# PROC099A_Decoupling_Caps_Reference.net
KiCad netlist of a schematic drawn in Altium Designer
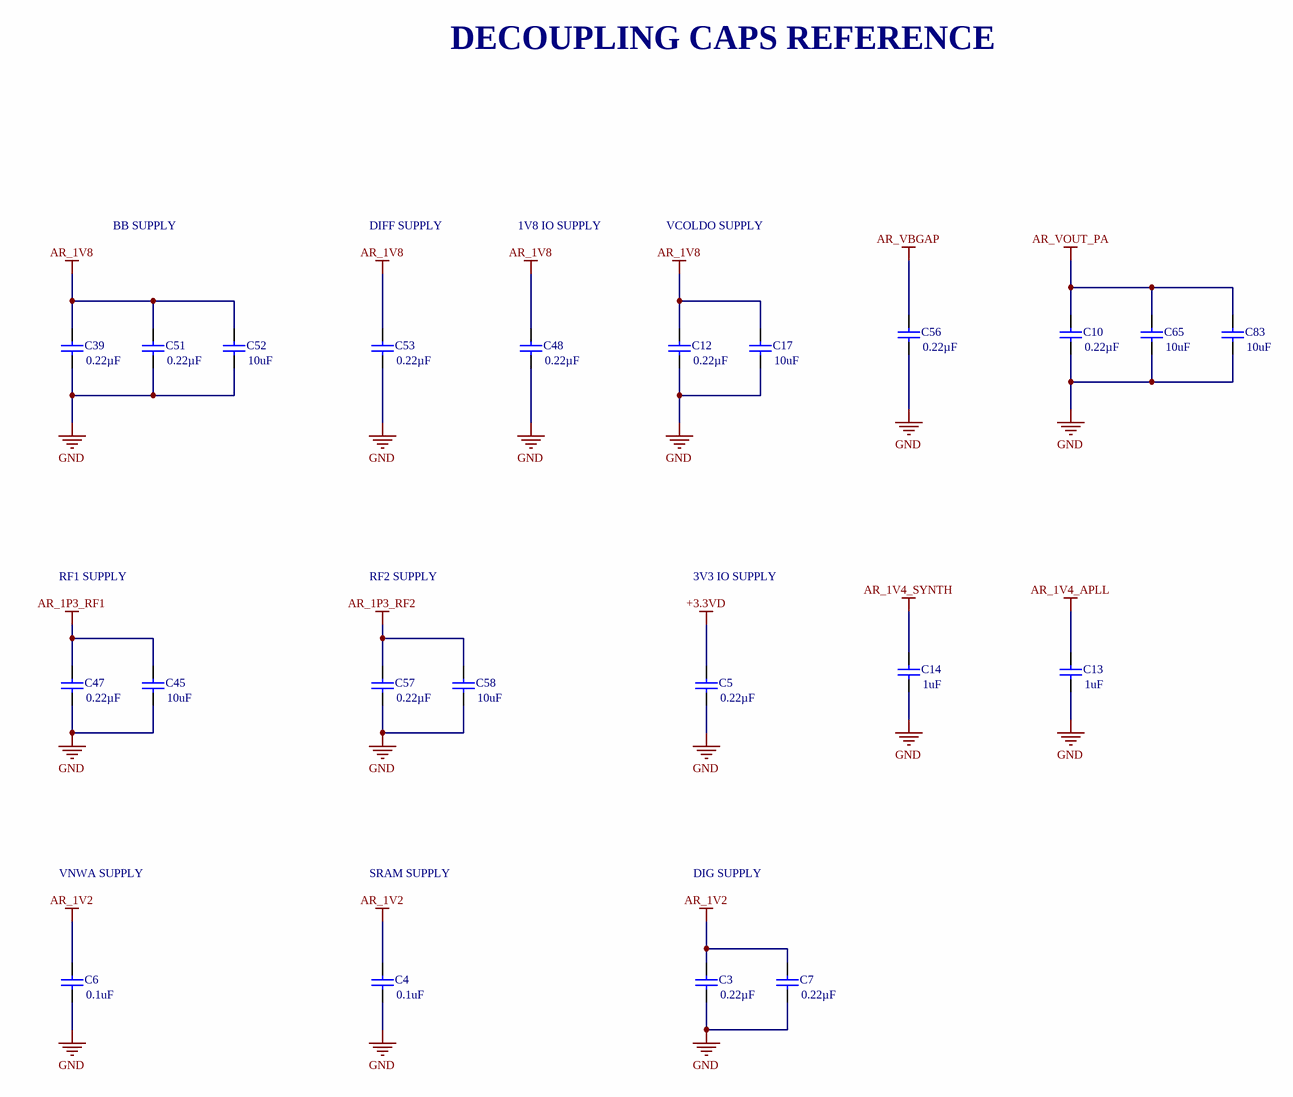
[diagram p0: PROC099A_Decoupling_Caps_Reference.SchDoc]

(export (version "E")
  (design (tool "Eeschema 10.0.6"))
  (components
    (comp (ref "C3")
      (value "GCM155R71C224KE02D")
      (footprint "0402L")
      (description "CAP, CERM, 0.22 µF, 16 V,+/- 10%, X7R, AEC-Q200 Grade 1, 0402")
      (fields (field (name "MANUFACTURER") "MuRata") (field (name "VALUEDISPLAYED") "0.22µF"))
      (libsource (lib "Altium Vault - TI") (part "CMP-0078265-1"))
    )
    (comp (ref "C4")
      (value "GCM155R71C104KA55D")
      (footprint "0402L")
      (description "CAP, CERM, 0.1 uF, 16 V, +/- 10%, X7R, 0402")
      (fields
        (field (name "MANUFACTURER") "MuRata")
        (field (name "VALUEDISPLAYED") "0.1uF")
        (field (name "PUBLISHER") "Texas Instruments")
      )
      (libsource (lib "Altium Vault - TI") (part "CMP-0006351-2"))
    )
    (comp (ref "C5")
      (value "GCM155R71C224KE02D")
      (footprint "0402L")
      (description "CAP, CERM, 0.22 µF, 16 V,+/- 10%, X7R, AEC-Q200 Grade 1, 0402")
      (fields (field (name "MANUFACTURER") "MuRata") (field (name "VALUEDISPLAYED") "0.22µF"))
      (libsource (lib "Altium Vault - TI") (part "CMP-0078265-1"))
    )
    (comp (ref "C6")
      (value "GCM155R71C104KA55D")
      (footprint "0402")
      (description "CAP, CERM, 0.1 uF, 16 V, +/- 10%, X7R, 0402")
      (fields
        (field (name "MANUFACTURER") "MuRata")
        (field (name "VALUEDISPLAYED") "0.1uF")
        (field (name "PUBLISHER") "Texas Instruments")
      )
      (libsource (lib "Altium Vault - TI") (part "Capacitor"))
    )
    (comp (ref "C7")
      (value "GCM155R71C224KE02D")
      (footprint "0402L")
      (description "CAP, CERM, 0.22 µF, 16 V,+/- 10%, X7R, AEC-Q200 Grade 1, 0402")
      (fields (field (name "MANUFACTURER") "MuRata") (field (name "VALUEDISPLAYED") "0.22µF"))
      (libsource (lib "Altium Vault - TI") (part "CMP-0078265-1"))
    )
    (comp (ref "C10")
      (value "GCM155R71C224KE02D")
      (footprint "0402")
      (description "CAP, CERM, 0.22 µF, 16 V,+/- 10%, X7R, AEC-Q200 Grade 1, 0402")
      (fields (field (name "MANUFACTURER") "MuRata") (field (name "VALUEDISPLAYED") "0.22µF"))
      (libsource (lib "Altium Vault - TI") (part "Capacitor"))
    )
    (comp (ref "C12")
      (value "GCM155R71C224KE02D")
      (footprint "0402")
      (description "CAP, CERM, 0.22 µF, 16 V,+/- 10%, X7R, AEC-Q200 Grade 1, 0402")
      (fields (field (name "MANUFACTURER") "MuRata") (field (name "VALUEDISPLAYED") "0.22µF"))
      (libsource (lib "Altium Vault - TI") (part "Capacitor"))
    )
    (comp (ref "C13")
      (value "GCM188R71C105KA64D")
      (footprint "0603")
      (description "CAP, CERM, 1 uF, 16 V, +/- 10%, X7R, AEC-Q200 Grade 1, 0603")
      (fields
        (field (name "MANUFACTURER") "MuRata")
        (field (name "VALUEDISPLAYED") "1uF")
        (field (name "PUBLISHER") "Texas Instruments")
      )
      (libsource (lib "Altium Vault - TI") (part "Capacitor"))
    )
    (comp (ref "C14")
      (value "GCM188R71C105KA64D")
      (footprint "0603")
      (description "CAP, CERM, 1 uF, 16 V, +/- 10%, X7R, AEC-Q200 Grade 1, 0603")
      (fields
        (field (name "MANUFACTURER") "MuRata")
        (field (name "VALUEDISPLAYED") "1uF")
        (field (name "PUBLISHER") "Texas Instruments")
      )
      (libsource (lib "Altium Vault - TI") (part "Capacitor"))
    )
    (comp (ref "C17")
      (value "GCM21BR71A106KE22L")
      (footprint "0805_HV")
      (description "CAP, CERM, 10 uF, 10 V, +/- 10%, X7R, 0805")
      (fields
        (field (name "MANUFACTURER") "MuRata")
        (field (name "VALUEDISPLAYED") "10uF")
        (field (name "PUBLISHER") "Texas Instruments")
      )
      (libsource (lib "Altium Vault - TI") (part "Capacitor"))
    )
    (comp (ref "C39")
      (value "GCM155R71C224KE02D")
      (footprint "0402L")
      (description "CAP, CERM, 0.22 µF, 16 V,+/- 10%, X7R, AEC-Q200 Grade 1, 0402")
      (fields (field (name "MANUFACTURER") "MuRata") (field (name "VALUEDISPLAYED") "0.22µF"))
      (libsource (lib "Altium Vault - TI") (part "CMP-0078265-1"))
    )
    (comp (ref "C45")
      (value "GCM21BR71A106KE22L")
      (footprint "0805_HV1")
      (description "CAP, CERM, 10 uF, 10 V, +/- 10%, X7R, 0805")
      (fields
        (field (name "MANUFACTURER") "MuRata")
        (field (name "VALUEDISPLAYED") "10uF")
        (field (name "PUBLISHER") "Texas Instruments")
      )
      (libsource (lib "Altium Vault - TI") (part "CMP-0008017-2"))
    )
    (comp (ref "C47")
      (value "GCM155R71C224KE02D")
      (footprint "0402L")
      (description "CAP, CERM, 0.22 µF, 16 V,+/- 10%, X7R, AEC-Q200 Grade 1, 0402")
      (fields (field (name "MANUFACTURER") "MuRata") (field (name "VALUEDISPLAYED") "0.22µF"))
      (libsource (lib "Altium Vault - TI") (part "CMP-0078265-1"))
    )
    (comp (ref "C48")
      (value "GCM155R71C224KE02D")
      (footprint "0402")
      (description "CAP, CERM, 0.22 µF, 16 V,+/- 10%, X7R, AEC-Q200 Grade 1, 0402")
      (fields (field (name "MANUFACTURER") "MuRata") (field (name "VALUEDISPLAYED") "0.22µF"))
      (libsource (lib "Altium Vault - TI") (part "Capacitor"))
    )
    (comp (ref "C51")
      (value "GCM155R71C224KE02D")
      (footprint "0402")
      (description "CAP, CERM, 0.22 µF, 16 V,+/- 10%, X7R, AEC-Q200 Grade 1, 0402")
      (fields (field (name "MANUFACTURER") "MuRata") (field (name "VALUEDISPLAYED") "0.22µF"))
      (libsource (lib "Altium Vault - TI") (part "Capacitor"))
    )
    (comp (ref "C52")
      (value "GCM21BR71A106KE22L")
      (footprint "0805_HV")
      (description "CAP, CERM, 10 uF, 10 V, +/- 10%, X7R, 0805")
      (fields
        (field (name "MANUFACTURER") "MuRata")
        (field (name "VALUEDISPLAYED") "10uF")
        (field (name "PUBLISHER") "Texas Instruments")
      )
      (libsource (lib "Altium Vault - TI") (part "Capacitor"))
    )
    (comp (ref "C53")
      (value "GCM155R71C224KE02D")
      (footprint "0402")
      (description "CAP, CERM, 0.22 µF, 16 V,+/- 10%, X7R, AEC-Q200 Grade 1, 0402")
      (fields (field (name "MANUFACTURER") "MuRata") (field (name "VALUEDISPLAYED") "0.22µF"))
      (libsource (lib "Altium Vault - TI") (part "Capacitor"))
    )
    (comp (ref "C56")
      (value "GCM155R71C224KE02D")
      (footprint "0402")
      (description "CAP, CERM, 0.22 µF, 16 V,+/- 10%, X7R, AEC-Q200 Grade 1, 0402")
      (fields (field (name "MANUFACTURER") "MuRata") (field (name "VALUEDISPLAYED") "0.22µF"))
      (libsource (lib "Altium Vault - TI") (part "Capacitor"))
    )
    (comp (ref "C57")
      (value "GCM155R71C224KE02D")
      (footprint "0402")
      (description "CAP, CERM, 0.22 µF, 16 V,+/- 10%, X7R, AEC-Q200 Grade 1, 0402")
      (fields (field (name "MANUFACTURER") "MuRata") (field (name "VALUEDISPLAYED") "0.22µF"))
      (libsource (lib "Altium Vault - TI") (part "Capacitor"))
    )
    (comp (ref "C58")
      (value "GCM21BR71A106KE22L")
      (footprint "0805")
      (description "CAP, CERM, 10 uF, 10 V, +/- 10%, X7R, 0805")
      (fields
        (field (name "MANUFACTURER") "MuRata")
        (field (name "VALUEDISPLAYED") "10uF")
        (field (name "PUBLISHER") "Texas Instruments")
      )
      (libsource (lib "Altium Vault - TI") (part "CMP-0008017-2"))
    )
    (comp (ref "C65")
      (value "GCM21BR71A106KE22L")
      (footprint "0805_HV")
      (description "CAP, CERM, 10 uF, 10 V, +/- 10%, X7R, 0805")
      (fields
        (field (name "MANUFACTURER") "MuRata")
        (field (name "VALUEDISPLAYED") "10uF")
        (field (name "PUBLISHER") "Texas Instruments")
      )
      (libsource (lib "Altium Vault - TI") (part "Capacitor"))
    )
    (comp (ref "C83")
      (value "GCM21BR71A106KE22L")
      (footprint "0805_HV")
      (description "CAP, CERM, 10 uF, 10 V, +/- 10%, X7R, 0805")
      (fields
        (field (name "MANUFACTURER") "MuRata")
        (field (name "VALUEDISPLAYED") "10uF")
        (field (name "PUBLISHER") "Texas Instruments")
      )
      (libsource (lib "Altium Vault - TI") (part "Capacitor"))
    )
  )
  (nets
    (net (code "1") (name "+3.3VD") (class "Default")
      (node (ref "C5") (pin "1") (pinfunction "1_1") (pintype "passive"))
    )
    (net (code "2") (name "AR_1P3_RF1") (class "Default")
      (node (ref "C45") (pin "1") (pinfunction "1_1") (pintype "passive"))
      (node (ref "C47") (pin "1") (pinfunction "1_1") (pintype "passive"))
    )
    (net (code "3") (name "AR_1P3_RF2") (class "Default")
      (node (ref "C57") (pin "1") (pinfunction "1_1") (pintype "passive"))
      (node (ref "C58") (pin "1") (pinfunction "1_1") (pintype "passive"))
    )
    (net (code "4") (name "AR_1V2") (class "Default")
      (node (ref "C3") (pin "1") (pinfunction "1_1") (pintype "passive"))
      (node (ref "C4") (pin "1") (pinfunction "1_1") (pintype "passive"))
      (node (ref "C6") (pin "1") (pinfunction "1_1") (pintype "passive"))
      (node (ref "C7") (pin "1") (pinfunction "1_1") (pintype "passive"))
    )
    (net (code "5") (name "AR_1V4_APLL") (class "Default")
      (node (ref "C13") (pin "1") (pinfunction "1_1") (pintype "passive"))
    )
    (net (code "6") (name "AR_1V4_SYNTH") (class "Default")
      (node (ref "C14") (pin "1") (pinfunction "1_1") (pintype "passive"))
    )
    (net (code "7") (name "AR_1V8") (class "Default")
      (node (ref "C12") (pin "1") (pinfunction "1_1") (pintype "passive"))
      (node (ref "C17") (pin "1") (pinfunction "1_1") (pintype "passive"))
      (node (ref "C39") (pin "1") (pinfunction "1_1") (pintype "passive"))
      (node (ref "C48") (pin "1") (pinfunction "1_1") (pintype "passive"))
      (node (ref "C51") (pin "1") (pinfunction "1_1") (pintype "passive"))
      (node (ref "C52") (pin "1") (pinfunction "1_1") (pintype "passive"))
      (node (ref "C53") (pin "1") (pinfunction "1_1") (pintype "passive"))
    )
    (net (code "8") (name "AR_VBGAP") (class "Default")
      (node (ref "C56") (pin "1") (pinfunction "1_1") (pintype "passive"))
    )
    (net (code "9") (name "AR_VOUT_PA") (class "Default")
      (node (ref "C10") (pin "1") (pinfunction "1_1") (pintype "passive"))
      (node (ref "C65") (pin "1") (pinfunction "1_1") (pintype "passive"))
      (node (ref "C83") (pin "1") (pinfunction "1_1") (pintype "passive"))
    )
    (net (code "10") (name "GND") (class "Default")
      (node (ref "C10") (pin "2") (pinfunction "2_2") (pintype "passive"))
      (node (ref "C12") (pin "2") (pinfunction "2_2") (pintype "passive"))
      (node (ref "C13") (pin "2") (pinfunction "2_2") (pintype "passive"))
      (node (ref "C14") (pin "2") (pinfunction "2_2") (pintype "passive"))
      (node (ref "C17") (pin "2") (pinfunction "2_2") (pintype "passive"))
      (node (ref "C3") (pin "2") (pinfunction "2_2") (pintype "passive"))
      (node (ref "C39") (pin "2") (pinfunction "2_2") (pintype "passive"))
      (node (ref "C4") (pin "2") (pinfunction "2_2") (pintype "passive"))
      (node (ref "C45") (pin "2") (pinfunction "2_2") (pintype "passive"))
      (node (ref "C47") (pin "2") (pinfunction "2_2") (pintype "passive"))
      (node (ref "C48") (pin "2") (pinfunction "2_2") (pintype "passive"))
      (node (ref "C5") (pin "2") (pinfunction "2_2") (pintype "passive"))
      (node (ref "C51") (pin "2") (pinfunction "2_2") (pintype "passive"))
      (node (ref "C52") (pin "2") (pinfunction "2_2") (pintype "passive"))
      (node (ref "C53") (pin "2") (pinfunction "2_2") (pintype "passive"))
      (node (ref "C56") (pin "2") (pinfunction "2_2") (pintype "passive"))
      (node (ref "C57") (pin "2") (pinfunction "2_2") (pintype "passive"))
      (node (ref "C58") (pin "2") (pinfunction "2_2") (pintype "passive"))
      (node (ref "C6") (pin "2") (pinfunction "2_2") (pintype "passive"))
      (node (ref "C65") (pin "2") (pinfunction "2_2") (pintype "passive"))
      (node (ref "C7") (pin "2") (pinfunction "2_2") (pintype "passive"))
      (node (ref "C83") (pin "2") (pinfunction "2_2") (pintype "passive"))
    )
  )
)
